# Voltage_Sense_Board.net
KiCad netlist of a schematic drawn in Altium Designer
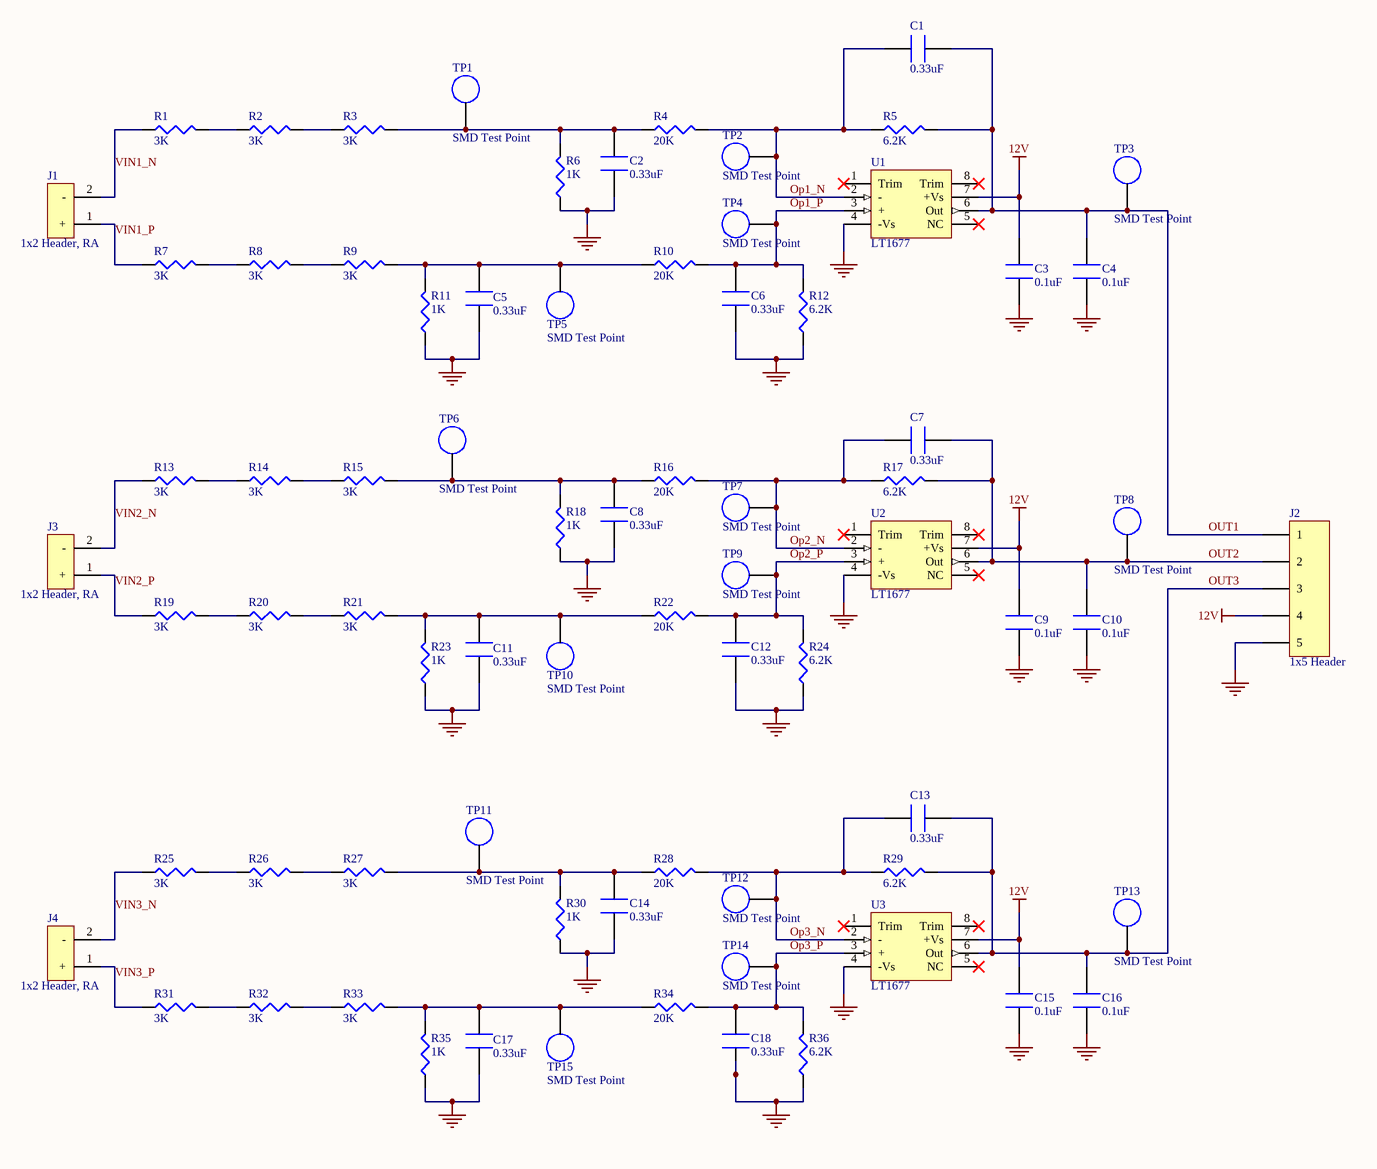
[diagram p0: Voltage Sense Board.SchDoc]

(export (version "E")
  (design (tool "Eeschema 10.0.6"))
  (components
    (comp (ref "C1")
      (value "0.33uF")
      (description "CAP CER 0.33UF 50V X7R 0805")
      (fields
        (field (name "MANUFACTURER") "Samsung")
        (field (name "MANUFACTURER PART NUMBER") "CL21B334KBFVPNE")
      )
      (libsource (lib "V_Sense_Schlib") (part "CL21B334KBFVPNE"))
    )
    (comp (ref "C2")
      (value "0.33uF")
      (description "CAP CER 0.33UF 50V X7R 0805")
      (fields
        (field (name "MANUFACTURER") "Samsung")
        (field (name "MANUFACTURER PART NUMBER") "CL21B334KBFVPNE")
      )
      (libsource (lib "V_Sense_Schlib") (part "CL21B334KBFVPNE"))
    )
    (comp (ref "C3")
      (value "0.1uF")
      (description "CAP CER 0.1UF 50V X7R 0805")
      (fields
        (field (name "MANUFACTURER") "Samsung")
        (field (name "MANUFACTURER PART NUMBER") "CL21B104KBCWPNC")
      )
      (libsource (lib "V_Sense_Schlib") (part "CL21B104KBCWPNC"))
    )
    (comp (ref "C4")
      (value "0.1uF")
      (description "CAP CER 0.1UF 50V X7R 0805")
      (fields
        (field (name "MANUFACTURER") "Samsung")
        (field (name "MANUFACTURER PART NUMBER") "CL21B104KBCWPNC")
      )
      (libsource (lib "V_Sense_Schlib") (part "CL21B104KBCWPNC"))
    )
    (comp (ref "C5")
      (value "0.33uF")
      (description "CAP CER 0.33UF 50V X7R 0805")
      (fields
        (field (name "MANUFACTURER") "Samsung")
        (field (name "MANUFACTURER PART NUMBER") "CL21B334KBFVPNE")
      )
      (libsource (lib "V_Sense_Schlib") (part "CL21B334KBFVPNE"))
    )
    (comp (ref "C6")
      (value "0.33uF")
      (description "CAP CER 0.33UF 50V X7R 0805")
      (fields
        (field (name "MANUFACTURER") "Samsung")
        (field (name "MANUFACTURER PART NUMBER") "CL21B334KBFVPNE")
      )
      (libsource (lib "V_Sense_Schlib") (part "CL21B334KBFVPNE"))
    )
    (comp (ref "C7")
      (value "0.33uF")
      (description "CAP CER 0.33UF 50V X7R 0805")
      (fields
        (field (name "MANUFACTURER") "Samsung")
        (field (name "MANUFACTURER PART NUMBER") "CL21B334KBFVPNE")
      )
      (libsource (lib "V_Sense_Schlib") (part "CL21B334KBFVPNE"))
    )
    (comp (ref "C8")
      (value "0.33uF")
      (description "CAP CER 0.33UF 50V X7R 0805")
      (fields
        (field (name "MANUFACTURER") "Samsung")
        (field (name "MANUFACTURER PART NUMBER") "CL21B334KBFVPNE")
      )
      (libsource (lib "V_Sense_Schlib") (part "CL21B334KBFVPNE"))
    )
    (comp (ref "C9")
      (value "0.1uF")
      (description "CAP CER 0.1UF 50V X7R 0805")
      (fields
        (field (name "MANUFACTURER") "Samsung")
        (field (name "MANUFACTURER PART NUMBER") "CL21B104KBCWPNC")
      )
      (libsource (lib "V_Sense_Schlib") (part "CL21B104KBCWPNC"))
    )
    (comp (ref "C10")
      (value "0.1uF")
      (description "CAP CER 0.1UF 50V X7R 0805")
      (fields
        (field (name "MANUFACTURER") "Samsung")
        (field (name "MANUFACTURER PART NUMBER") "CL21B104KBCWPNC")
      )
      (libsource (lib "V_Sense_Schlib") (part "CL21B104KBCWPNC"))
    )
    (comp (ref "C11")
      (value "0.33uF")
      (description "CAP CER 0.33UF 50V X7R 0805")
      (fields
        (field (name "MANUFACTURER") "Samsung")
        (field (name "MANUFACTURER PART NUMBER") "CL21B334KBFVPNE")
      )
      (libsource (lib "V_Sense_Schlib") (part "CL21B334KBFVPNE"))
    )
    (comp (ref "C12")
      (value "0.33uF")
      (description "CAP CER 0.33UF 50V X7R 0805")
      (fields
        (field (name "MANUFACTURER") "Samsung")
        (field (name "MANUFACTURER PART NUMBER") "CL21B334KBFVPNE")
      )
      (libsource (lib "V_Sense_Schlib") (part "CL21B334KBFVPNE"))
    )
    (comp (ref "C13")
      (value "0.33uF")
      (description "CAP CER 0.33UF 50V X7R 0805")
      (fields
        (field (name "MANUFACTURER") "Samsung")
        (field (name "MANUFACTURER PART NUMBER") "CL21B334KBFVPNE")
      )
      (libsource (lib "V_Sense_Schlib") (part "CL21B334KBFVPNE"))
    )
    (comp (ref "C14")
      (value "0.33uF")
      (description "CAP CER 0.33UF 50V X7R 0805")
      (fields
        (field (name "MANUFACTURER") "Samsung")
        (field (name "MANUFACTURER PART NUMBER") "CL21B334KBFVPNE")
      )
      (libsource (lib "V_Sense_Schlib") (part "CL21B334KBFVPNE"))
    )
    (comp (ref "C15")
      (value "0.1uF")
      (description "CAP CER 0.1UF 50V X7R 0805")
      (fields
        (field (name "MANUFACTURER") "Samsung")
        (field (name "MANUFACTURER PART NUMBER") "CL21B104KBCWPNC")
      )
      (libsource (lib "V_Sense_Schlib") (part "CL21B104KBCWPNC"))
    )
    (comp (ref "C16")
      (value "0.1uF")
      (description "CAP CER 0.1UF 50V X7R 0805")
      (fields
        (field (name "MANUFACTURER") "Samsung")
        (field (name "MANUFACTURER PART NUMBER") "CL21B104KBCWPNC")
      )
      (libsource (lib "V_Sense_Schlib") (part "CL21B104KBCWPNC"))
    )
    (comp (ref "C17")
      (value "0.33uF")
      (description "CAP CER 0.33UF 50V X7R 0805")
      (fields
        (field (name "MANUFACTURER") "Samsung")
        (field (name "MANUFACTURER PART NUMBER") "CL21B334KBFVPNE")
      )
      (libsource (lib "V_Sense_Schlib") (part "CL21B334KBFVPNE"))
    )
    (comp (ref "C18")
      (value "0.33uF")
      (description "CAP CER 0.33UF 50V X7R 0805")
      (fields
        (field (name "MANUFACTURER") "Samsung")
        (field (name "MANUFACTURER PART NUMBER") "CL21B334KBFVPNE")
      )
      (libsource (lib "V_Sense_Schlib") (part "CL21B334KBFVPNE"))
    )
    (comp (ref "J1")
      (value "1x2 Header, RA")
      (description "HEADER, RIGHT ANGLE, 2WAY")
      (fields (field (name "MANUFACTURER") "Molex") (field (name "MANUFACTURER PART NUMBER") "43650-0205"))
      (libsource (lib "V_Sense_Schlib") (part "43650-0205"))
    )
    (comp (ref "J2")
      (value "1x5 Header")
      (description "CONN HEADER VERT SGL 5POS GOLD")
      (fields (field (name "MANUFACTURER") "3M") (field (name "MANUFACTURER PART NUMBER") "961105-6404-AR"))
      (libsource (lib "V_Sense_Schlib") (part "961105-6404-AR"))
    )
    (comp (ref "J3")
      (value "1x2 Header, RA")
      (description "HEADER, RIGHT ANGLE, 2WAY")
      (fields (field (name "MANUFACTURER") "Molex") (field (name "MANUFACTURER PART NUMBER") "43650-0205"))
      (libsource (lib "V_Sense_Schlib") (part "43650-0205"))
    )
    (comp (ref "J4")
      (value "1x2 Header, RA")
      (description "HEADER, RIGHT ANGLE, 2WAY")
      (fields (field (name "MANUFACTURER") "Molex") (field (name "MANUFACTURER PART NUMBER") "43650-0205"))
      (libsource (lib "V_Sense_Schlib") (part "43650-0205"))
    )
    (comp (ref "R1")
      (value "3K")
      (description "RES SMD 3K OHM 1% 0.4W 0805")
      (fields (field (name "MANUFACTURER") "Rohm") (field (name "MANUFACTURER PART NUMBER") "ESR10EZPF3001"))
      (libsource (lib "V_Sense_Schlib") (part "ESR10EZPF3001"))
    )
    (comp (ref "R2")
      (value "3K")
      (description "RES SMD 3K OHM 1% 0.4W 0805")
      (fields (field (name "MANUFACTURER") "Rohm") (field (name "MANUFACTURER PART NUMBER") "ESR10EZPF3001"))
      (libsource (lib "V_Sense_Schlib") (part "ESR10EZPF3001"))
    )
    (comp (ref "R3")
      (value "3K")
      (description "RES SMD 3K OHM 1% 0.4W 0805")
      (fields (field (name "MANUFACTURER") "Rohm") (field (name "MANUFACTURER PART NUMBER") "ESR10EZPF3001"))
      (libsource (lib "V_Sense_Schlib") (part "ESR10EZPF3001"))
    )
    (comp (ref "R4")
      (value "20K")
      (description "RES 20K OHM 0.1% 1/5W 0805")
      (fields
        (field (name "MANUFACTURER") "Vishay Dale")
        (field (name "MANUFACTURER PART NUMBER") "TNPW080520K0BEEA")
      )
      (libsource (lib "V_Sense_Schlib") (part "TNPW080520K0BEEA"))
    )
    (comp (ref "R5")
      (value "6.2K")
      (description "RES SMD 6.2K OHM 0.1% 1/8W 0805")
      (fields
        (field (name "MANUFACTURER") "Panasonic")
        (field (name "MANUFACTURER PART NUMBER") "ERA6AEB622V")
      )
      (libsource (lib "V_Sense_Schlib") (part "ERA6AEB622V"))
    )
    (comp (ref "R6")
      (value "1K")
      (description "RES SMD 1K OHM 0.1% 1/4W 0805")
      (fields
        (field (name "MANUFACTURER") "TE Connectivity")
        (field (name "MANUFACTURER PART NUMBER") "1-2176092-8")
      )
      (libsource (lib "V_Sense_Schlib") (part "1-2176092-8"))
    )
    (comp (ref "R7")
      (value "3K")
      (description "RES SMD 3K OHM 1% 0.4W 0805")
      (fields (field (name "MANUFACTURER") "Rohm") (field (name "MANUFACTURER PART NUMBER") "ESR10EZPF3001"))
      (libsource (lib "V_Sense_Schlib") (part "ESR10EZPF3001"))
    )
    (comp (ref "R8")
      (value "3K")
      (description "RES SMD 3K OHM 1% 0.4W 0805")
      (fields (field (name "MANUFACTURER") "Rohm") (field (name "MANUFACTURER PART NUMBER") "ESR10EZPF3001"))
      (libsource (lib "V_Sense_Schlib") (part "ESR10EZPF3001"))
    )
    (comp (ref "R9")
      (value "3K")
      (description "RES SMD 3K OHM 1% 0.4W 0805")
      (fields (field (name "MANUFACTURER") "Rohm") (field (name "MANUFACTURER PART NUMBER") "ESR10EZPF3001"))
      (libsource (lib "V_Sense_Schlib") (part "ESR10EZPF3001"))
    )
    (comp (ref "R10")
      (value "20K")
      (description "RES 20K OHM 0.1% 1/5W 0805")
      (fields
        (field (name "MANUFACTURER") "Vishay Dale")
        (field (name "MANUFACTURER PART NUMBER") "TNPW080520K0BEEA")
      )
      (libsource (lib "V_Sense_Schlib") (part "TNPW080520K0BEEA"))
    )
    (comp (ref "R11")
      (value "1K")
      (description "RES SMD 1K OHM 0.1% 1/4W 0805")
      (fields
        (field (name "MANUFACTURER") "TE Connectivity")
        (field (name "MANUFACTURER PART NUMBER") "1-2176092-8")
      )
      (libsource (lib "V_Sense_Schlib") (part "1-2176092-8"))
    )
    (comp (ref "R12")
      (value "6.2K")
      (description "RES SMD 6.2K OHM 0.1% 1/8W 0805")
      (fields
        (field (name "MANUFACTURER") "Panasonic")
        (field (name "MANUFACTURER PART NUMBER") "ERA6AEB622V")
      )
      (libsource (lib "V_Sense_Schlib") (part "ERA6AEB622V"))
    )
    (comp (ref "R13")
      (value "3K")
      (description "RES SMD 3K OHM 1% 0.4W 0805")
      (fields (field (name "MANUFACTURER") "Rohm") (field (name "MANUFACTURER PART NUMBER") "ESR10EZPF3001"))
      (libsource (lib "V_Sense_Schlib") (part "ESR10EZPF3001"))
    )
    (comp (ref "R14")
      (value "3K")
      (description "RES SMD 3K OHM 1% 0.4W 0805")
      (fields (field (name "MANUFACTURER") "Rohm") (field (name "MANUFACTURER PART NUMBER") "ESR10EZPF3001"))
      (libsource (lib "V_Sense_Schlib") (part "ESR10EZPF3001"))
    )
    (comp (ref "R15")
      (value "3K")
      (description "RES SMD 3K OHM 1% 0.4W 0805")
      (fields (field (name "MANUFACTURER") "Rohm") (field (name "MANUFACTURER PART NUMBER") "ESR10EZPF3001"))
      (libsource (lib "V_Sense_Schlib") (part "ESR10EZPF3001"))
    )
    (comp (ref "R16")
      (value "20K")
      (description "RES 20K OHM 0.1% 1/5W 0805")
      (fields
        (field (name "MANUFACTURER") "Vishay Dale")
        (field (name "MANUFACTURER PART NUMBER") "TNPW080520K0BEEA")
      )
      (libsource (lib "V_Sense_Schlib") (part "TNPW080520K0BEEA"))
    )
    (comp (ref "R17")
      (value "6.2K")
      (description "RES SMD 6.2K OHM 0.1% 1/8W 0805")
      (fields
        (field (name "MANUFACTURER") "Panasonic")
        (field (name "MANUFACTURER PART NUMBER") "ERA6AEB622V")
      )
      (libsource (lib "V_Sense_Schlib") (part "ERA6AEB622V"))
    )
    (comp (ref "R18")
      (value "1K")
      (description "RES SMD 1K OHM 0.1% 1/4W 0805")
      (fields
        (field (name "MANUFACTURER") "TE Connectivity")
        (field (name "MANUFACTURER PART NUMBER") "1-2176092-8")
      )
      (libsource (lib "V_Sense_Schlib") (part "1-2176092-8"))
    )
    (comp (ref "R19")
      (value "3K")
      (description "RES SMD 3K OHM 1% 0.4W 0805")
      (fields (field (name "MANUFACTURER") "Rohm") (field (name "MANUFACTURER PART NUMBER") "ESR10EZPF3001"))
      (libsource (lib "V_Sense_Schlib") (part "ESR10EZPF3001"))
    )
    (comp (ref "R20")
      (value "3K")
      (description "RES SMD 3K OHM 1% 0.4W 0805")
      (fields (field (name "MANUFACTURER") "Rohm") (field (name "MANUFACTURER PART NUMBER") "ESR10EZPF3001"))
      (libsource (lib "V_Sense_Schlib") (part "ESR10EZPF3001"))
    )
    (comp (ref "R21")
      (value "3K")
      (description "RES SMD 3K OHM 1% 0.4W 0805")
      (fields (field (name "MANUFACTURER") "Rohm") (field (name "MANUFACTURER PART NUMBER") "ESR10EZPF3001"))
      (libsource (lib "V_Sense_Schlib") (part "ESR10EZPF3001"))
    )
    (comp (ref "R22")
      (value "20K")
      (description "RES 20K OHM 0.1% 1/5W 0805")
      (fields
        (field (name "MANUFACTURER") "Vishay Dale")
        (field (name "MANUFACTURER PART NUMBER") "TNPW080520K0BEEA")
      )
      (libsource (lib "V_Sense_Schlib") (part "TNPW080520K0BEEA"))
    )
    (comp (ref "R23")
      (value "1K")
      (description "RES SMD 1K OHM 0.1% 1/4W 0805")
      (fields
        (field (name "MANUFACTURER") "TE Connectivity")
        (field (name "MANUFACTURER PART NUMBER") "1-2176092-8")
      )
      (libsource (lib "V_Sense_Schlib") (part "1-2176092-8"))
    )
    (comp (ref "R24")
      (value "6.2K")
      (description "RES SMD 6.2K OHM 0.1% 1/8W 0805")
      (fields
        (field (name "MANUFACTURER") "Panasonic")
        (field (name "MANUFACTURER PART NUMBER") "ERA6AEB622V")
      )
      (libsource (lib "V_Sense_Schlib") (part "ERA6AEB622V"))
    )
    (comp (ref "R25")
      (value "3K")
      (description "RES SMD 3K OHM 1% 0.4W 0805")
      (fields (field (name "MANUFACTURER") "Rohm") (field (name "MANUFACTURER PART NUMBER") "ESR10EZPF3001"))
      (libsource (lib "V_Sense_Schlib") (part "ESR10EZPF3001"))
    )
    (comp (ref "R26")
      (value "3K")
      (description "RES SMD 3K OHM 1% 0.4W 0805")
      (fields (field (name "MANUFACTURER") "Rohm") (field (name "MANUFACTURER PART NUMBER") "ESR10EZPF3001"))
      (libsource (lib "V_Sense_Schlib") (part "ESR10EZPF3001"))
    )
    (comp (ref "R27")
      (value "3K")
      (description "RES SMD 3K OHM 1% 0.4W 0805")
      (fields (field (name "MANUFACTURER") "Rohm") (field (name "MANUFACTURER PART NUMBER") "ESR10EZPF3001"))
      (libsource (lib "V_Sense_Schlib") (part "ESR10EZPF3001"))
    )
    (comp (ref "R28")
      (value "20K")
      (description "RES 20K OHM 0.1% 1/5W 0805")
      (fields
        (field (name "MANUFACTURER") "Vishay Dale")
        (field (name "MANUFACTURER PART NUMBER") "TNPW080520K0BEEA")
      )
      (libsource (lib "V_Sense_Schlib") (part "TNPW080520K0BEEA"))
    )
    (comp (ref "R29")
      (value "6.2K")
      (description "RES SMD 6.2K OHM 0.1% 1/8W 0805")
      (fields
        (field (name "MANUFACTURER") "Panasonic")
        (field (name "MANUFACTURER PART NUMBER") "ERA6AEB622V")
      )
      (libsource (lib "V_Sense_Schlib") (part "ERA6AEB622V"))
    )
    (comp (ref "R30")
      (value "1K")
      (description "RES SMD 1K OHM 0.1% 1/4W 0805")
      (fields
        (field (name "MANUFACTURER") "TE Connectivity")
        (field (name "MANUFACTURER PART NUMBER") "1-2176092-8")
      )
      (libsource (lib "V_Sense_Schlib") (part "1-2176092-8"))
    )
    (comp (ref "R31")
      (value "3K")
      (description "RES SMD 3K OHM 1% 0.4W 0805")
      (fields (field (name "MANUFACTURER") "Rohm") (field (name "MANUFACTURER PART NUMBER") "ESR10EZPF3001"))
      (libsource (lib "V_Sense_Schlib") (part "ESR10EZPF3001"))
    )
    (comp (ref "R32")
      (value "3K")
      (description "RES SMD 3K OHM 1% 0.4W 0805")
      (fields (field (name "MANUFACTURER") "Rohm") (field (name "MANUFACTURER PART NUMBER") "ESR10EZPF3001"))
      (libsource (lib "V_Sense_Schlib") (part "ESR10EZPF3001"))
    )
    (comp (ref "R33")
      (value "3K")
      (description "RES SMD 3K OHM 1% 0.4W 0805")
      (fields (field (name "MANUFACTURER") "Rohm") (field (name "MANUFACTURER PART NUMBER") "ESR10EZPF3001"))
      (libsource (lib "V_Sense_Schlib") (part "ESR10EZPF3001"))
    )
    (comp (ref "R34")
      (value "20K")
      (description "RES 20K OHM 0.1% 1/5W 0805")
      (fields
        (field (name "MANUFACTURER") "Vishay Dale")
        (field (name "MANUFACTURER PART NUMBER") "TNPW080520K0BEEA")
      )
      (libsource (lib "V_Sense_Schlib") (part "TNPW080520K0BEEA"))
    )
    (comp (ref "R35")
      (value "1K")
      (description "RES SMD 1K OHM 0.1% 1/4W 0805")
      (fields
        (field (name "MANUFACTURER") "TE Connectivity")
        (field (name "MANUFACTURER PART NUMBER") "1-2176092-8")
      )
      (libsource (lib "V_Sense_Schlib") (part "1-2176092-8"))
    )
    (comp (ref "R36")
      (value "6.2K")
      (description "RES SMD 6.2K OHM 0.1% 1/8W 0805")
      (fields
        (field (name "MANUFACTURER") "Panasonic")
        (field (name "MANUFACTURER PART NUMBER") "ERA6AEB622V")
      )
      (libsource (lib "V_Sense_Schlib") (part "ERA6AEB622V"))
    )
    (comp (ref "TP1")
      (value "SMD Test Point")
      (description "Phosphor Bronze Contact Miniature Silver Plated Surface Mount Test Points")
      (fields
        (field (name "MANUFACTURER") "Keystone Electronics")
        (field (name "MANUFACTURER PART NUMBER") "5019")
      )
      (libsource (lib "V_Sense_Schlib") (part "5019"))
    )
    (comp (ref "TP2")
      (value "SMD Test Point")
      (description "Phosphor Bronze Contact Miniature Silver Plated Surface Mount Test Points")
      (fields
        (field (name "MANUFACTURER") "Keystone Electronics")
        (field (name "MANUFACTURER PART NUMBER") "5019")
      )
      (libsource (lib "V_Sense_Schlib") (part "5019"))
    )
    (comp (ref "TP3")
      (value "SMD Test Point")
      (description "Phosphor Bronze Contact Miniature Silver Plated Surface Mount Test Points")
      (fields
        (field (name "MANUFACTURER") "Keystone Electronics")
        (field (name "MANUFACTURER PART NUMBER") "5019")
      )
      (libsource (lib "V_Sense_Schlib") (part "5019"))
    )
    (comp (ref "TP4")
      (value "SMD Test Point")
      (description "Phosphor Bronze Contact Miniature Silver Plated Surface Mount Test Points")
      (fields
        (field (name "MANUFACTURER") "Keystone Electronics")
        (field (name "MANUFACTURER PART NUMBER") "5019")
      )
      (libsource (lib "V_Sense_Schlib") (part "5019"))
    )
    (comp (ref "TP5")
      (value "SMD Test Point")
      (description "Phosphor Bronze Contact Miniature Silver Plated Surface Mount Test Points")
      (fields
        (field (name "MANUFACTURER") "Keystone Electronics")
        (field (name "MANUFACTURER PART NUMBER") "5019")
      )
      (libsource (lib "V_Sense_Schlib") (part "5019"))
    )
    (comp (ref "TP6")
      (value "SMD Test Point")
      (description "Phosphor Bronze Contact Miniature Silver Plated Surface Mount Test Points")
      (fields
        (field (name "MANUFACTURER") "Keystone Electronics")
        (field (name "MANUFACTURER PART NUMBER") "5019")
      )
      (libsource (lib "V_Sense_Schlib") (part "5019"))
    )
    (comp (ref "TP7")
      (value "SMD Test Point")
      (description "Phosphor Bronze Contact Miniature Silver Plated Surface Mount Test Points")
      (fields
        (field (name "MANUFACTURER") "Keystone Electronics")
        (field (name "MANUFACTURER PART NUMBER") "5019")
      )
      (libsource (lib "V_Sense_Schlib") (part "5019"))
    )
    (comp (ref "TP8")
      (value "SMD Test Point")
      (description "Phosphor Bronze Contact Miniature Silver Plated Surface Mount Test Points")
      (fields
        (field (name "MANUFACTURER") "Keystone Electronics")
        (field (name "MANUFACTURER PART NUMBER") "5019")
      )
      (libsource (lib "V_Sense_Schlib") (part "5019"))
    )
    (comp (ref "TP9")
      (value "SMD Test Point")
      (description "Phosphor Bronze Contact Miniature Silver Plated Surface Mount Test Points")
      (fields
        (field (name "MANUFACTURER") "Keystone Electronics")
        (field (name "MANUFACTURER PART NUMBER") "5019")
      )
      (libsource (lib "V_Sense_Schlib") (part "5019"))
    )
    (comp (ref "TP10")
      (value "SMD Test Point")
      (description "Phosphor Bronze Contact Miniature Silver Plated Surface Mount Test Points")
      (fields
        (field (name "MANUFACTURER") "Keystone Electronics")
        (field (name "MANUFACTURER PART NUMBER") "5019")
      )
      (libsource (lib "V_Sense_Schlib") (part "5019"))
    )
    (comp (ref "TP11")
      (value "SMD Test Point")
      (description "Phosphor Bronze Contact Miniature Silver Plated Surface Mount Test Points")
      (fields
        (field (name "MANUFACTURER") "Keystone Electronics")
        (field (name "MANUFACTURER PART NUMBER") "5019")
      )
      (libsource (lib "V_Sense_Schlib") (part "5019"))
    )
    (comp (ref "TP12")
      (value "SMD Test Point")
      (description "Phosphor Bronze Contact Miniature Silver Plated Surface Mount Test Points")
      (fields
        (field (name "MANUFACTURER") "Keystone Electronics")
        (field (name "MANUFACTURER PART NUMBER") "5019")
      )
      (libsource (lib "V_Sense_Schlib") (part "5019"))
    )
    (comp (ref "TP13")
      (value "SMD Test Point")
      (description "Phosphor Bronze Contact Miniature Silver Plated Surface Mount Test Points")
      (fields
        (field (name "MANUFACTURER") "Keystone Electronics")
        (field (name "MANUFACTURER PART NUMBER") "5019")
      )
      (libsource (lib "V_Sense_Schlib") (part "5019"))
    )
    (comp (ref "TP14")
      (value "SMD Test Point")
      (description "Phosphor Bronze Contact Miniature Silver Plated Surface Mount Test Points")
      (fields
        (field (name "MANUFACTURER") "Keystone Electronics")
        (field (name "MANUFACTURER PART NUMBER") "5019")
      )
      (libsource (lib "V_Sense_Schlib") (part "5019"))
    )
    (comp (ref "TP15")
      (value "SMD Test Point")
      (description "Phosphor Bronze Contact Miniature Silver Plated Surface Mount Test Points")
      (fields
        (field (name "MANUFACTURER") "Keystone Electronics")
        (field (name "MANUFACTURER PART NUMBER") "5019")
      )
      (libsource (lib "V_Sense_Schlib") (part "5019"))
    )
    (comp (ref "U1")
      (value "LT1677")
      (description "IC OPAMP GP 7.2MHZ RRO 8SO")
      (fields
        (field (name "MANUFACTURER") "Analog Devices / Linear Technology")
        (field (name "MANUFACTURER PART NUMBER") "LT1677IS8#TRPBF")
      )
      (libsource (lib "V_Sense_Schlib") (part "LT1677IS8#TRPBF"))
    )
    (comp (ref "U2")
      (value "LT1677")
      (description "IC OPAMP GP 7.2MHZ RRO 8SO")
      (fields
        (field (name "MANUFACTURER") "Analog Devices / Linear Technology")
        (field (name "MANUFACTURER PART NUMBER") "LT1677IS8#TRPBF")
      )
      (libsource (lib "V_Sense_Schlib") (part "LT1677IS8#TRPBF"))
    )
    (comp (ref "U3")
      (value "LT1677")
      (description "IC OPAMP GP 7.2MHZ RRO 8SO")
      (fields
        (field (name "MANUFACTURER") "Analog Devices / Linear Technology")
        (field (name "MANUFACTURER PART NUMBER") "LT1677IS8#TRPBF")
      )
      (libsource (lib "V_Sense_Schlib") (part "LT1677IS8#TRPBF"))
    )
  )
  (nets
    (net (code "1") (name "/OUT1") (class "Default")
      (node (ref "C1") (pin "2") (pinfunction "2_2") (pintype "passive"))
      (node (ref "C4") (pin "2") (pinfunction "2_2") (pintype "passive"))
      (node (ref "J2") (pin "1") (pinfunction "1_1") (pintype "passive"))
      (node (ref "R5") (pin "2") (pinfunction "2_2") (pintype "passive"))
      (node (ref "TP3") (pin "1") (pinfunction "1_1") (pintype "passive"))
      (node (ref "U1") (pin "6") (pinfunction "Out_6") (pintype "output"))
    )
    (net (code "2") (name "/OUT2") (class "Default")
      (node (ref "C10") (pin "2") (pinfunction "2_2") (pintype "passive"))
      (node (ref "C7") (pin "2") (pinfunction "2_2") (pintype "passive"))
      (node (ref "J2") (pin "2") (pinfunction "2_2") (pintype "passive"))
      (node (ref "R17") (pin "2") (pinfunction "2_2") (pintype "passive"))
      (node (ref "TP8") (pin "1") (pinfunction "1_1") (pintype "passive"))
      (node (ref "U2") (pin "6") (pinfunction "Out_6") (pintype "output"))
    )
    (net (code "3") (name "/OUT3") (class "Default")
      (node (ref "C13") (pin "2") (pinfunction "2_2") (pintype "passive"))
      (node (ref "C16") (pin "2") (pinfunction "2_2") (pintype "passive"))
      (node (ref "J2") (pin "3") (pinfunction "3_3") (pintype "passive"))
      (node (ref "R29") (pin "2") (pinfunction "2_2") (pintype "passive"))
      (node (ref "TP13") (pin "1") (pinfunction "1_1") (pintype "passive"))
      (node (ref "U3") (pin "6") (pinfunction "Out_6") (pintype "output"))
    )
    (net (code "4") (name "/Op1_N") (class "Default")
      (node (ref "C1") (pin "1") (pinfunction "1_1") (pintype "passive"))
      (node (ref "R4") (pin "2") (pinfunction "2_2") (pintype "passive"))
      (node (ref "R5") (pin "1") (pinfunction "1_1") (pintype "passive"))
      (node (ref "TP2") (pin "1") (pinfunction "1_1") (pintype "passive"))
      (node (ref "U1") (pin "2") (pinfunction "-_2") (pintype "input"))
    )
    (net (code "5") (name "/Op1_P") (class "Default")
      (node (ref "C6") (pin "2") (pinfunction "2_2") (pintype "passive"))
      (node (ref "R10") (pin "2") (pinfunction "2_2") (pintype "passive"))
      (node (ref "R12") (pin "2") (pinfunction "2_2") (pintype "passive"))
      (node (ref "TP4") (pin "1") (pinfunction "1_1") (pintype "passive"))
      (node (ref "U1") (pin "3") (pinfunction "+_3") (pintype "input"))
    )
    (net (code "6") (name "/Op2_N") (class "Default")
      (node (ref "C7") (pin "1") (pinfunction "1_1") (pintype "passive"))
      (node (ref "R16") (pin "2") (pinfunction "2_2") (pintype "passive"))
      (node (ref "R17") (pin "1") (pinfunction "1_1") (pintype "passive"))
      (node (ref "TP7") (pin "1") (pinfunction "1_1") (pintype "passive"))
      (node (ref "U2") (pin "2") (pinfunction "-_2") (pintype "input"))
    )
    (net (code "7") (name "/Op2_P") (class "Default")
      (node (ref "C12") (pin "2") (pinfunction "2_2") (pintype "passive"))
      (node (ref "R22") (pin "2") (pinfunction "2_2") (pintype "passive"))
      (node (ref "R24") (pin "2") (pinfunction "2_2") (pintype "passive"))
      (node (ref "TP9") (pin "1") (pinfunction "1_1") (pintype "passive"))
      (node (ref "U2") (pin "3") (pinfunction "+_3") (pintype "input"))
    )
    (net (code "8") (name "/Op3_N") (class "Default")
      (node (ref "C13") (pin "1") (pinfunction "1_1") (pintype "passive"))
      (node (ref "R28") (pin "2") (pinfunction "2_2") (pintype "passive"))
      (node (ref "R29") (pin "1") (pinfunction "1_1") (pintype "passive"))
      (node (ref "TP12") (pin "1") (pinfunction "1_1") (pintype "passive"))
      (node (ref "U3") (pin "2") (pinfunction "-_2") (pintype "input"))
    )
    (net (code "9") (name "/Op3_P") (class "Default")
      (node (ref "C18") (pin "2") (pinfunction "2_2") (pintype "passive"))
      (node (ref "R34") (pin "2") (pinfunction "2_2") (pintype "passive"))
      (node (ref "R36") (pin "2") (pinfunction "2_2") (pintype "passive"))
      (node (ref "TP14") (pin "1") (pinfunction "1_1") (pintype "passive"))
      (node (ref "U3") (pin "3") (pinfunction "+_3") (pintype "input"))
    )
    (net (code "10") (name "/VIN1_N") (class "Default")
      (node (ref "J1") (pin "2") (pinfunction "-_2") (pintype "passive"))
      (node (ref "R1") (pin "1") (pinfunction "1_1") (pintype "passive"))
    )
    (net (code "11") (name "/VIN1_P") (class "Default")
      (node (ref "J1") (pin "1") (pinfunction "+_1") (pintype "passive"))
      (node (ref "R7") (pin "1") (pinfunction "1_1") (pintype "passive"))
    )
    (net (code "12") (name "/VIN2_N") (class "Default")
      (node (ref "J3") (pin "2") (pinfunction "-_2") (pintype "passive"))
      (node (ref "R13") (pin "1") (pinfunction "1_1") (pintype "passive"))
    )
    (net (code "13") (name "/VIN2_P") (class "Default")
      (node (ref "J3") (pin "1") (pinfunction "+_1") (pintype "passive"))
      (node (ref "R19") (pin "1") (pinfunction "1_1") (pintype "passive"))
    )
    (net (code "14") (name "/VIN3_N") (class "Default")
      (node (ref "J4") (pin "2") (pinfunction "-_2") (pintype "passive"))
      (node (ref "R25") (pin "1") (pinfunction "1_1") (pintype "passive"))
    )
    (net (code "15") (name "/VIN3_P") (class "Default")
      (node (ref "J4") (pin "1") (pinfunction "+_1") (pintype "passive"))
      (node (ref "R31") (pin "1") (pinfunction "1_1") (pintype "passive"))
    )
    (net (code "16") (name "12V") (class "Default")
      (node (ref "C15") (pin "2") (pinfunction "2_2") (pintype "passive"))
      (node (ref "C3") (pin "2") (pinfunction "2_2") (pintype "passive"))
      (node (ref "C9") (pin "2") (pinfunction "2_2") (pintype "passive"))
      (node (ref "J2") (pin "4") (pinfunction "4_4") (pintype "passive"))
      (node (ref "U1") (pin "7") (pinfunction "+Vs_7") (pintype "power_in"))
      (node (ref "U2") (pin "7") (pinfunction "+Vs_7") (pintype "power_in"))
      (node (ref "U3") (pin "7") (pinfunction "+Vs_7") (pintype "power_in"))
    )
    (net (code "17") (name "GND") (class "Default")
      (node (ref "C10") (pin "1") (pinfunction "1_1") (pintype "passive"))
      (node (ref "C11") (pin "1") (pinfunction "1_1") (pintype "passive"))
      (node (ref "C12") (pin "1") (pinfunction "1_1") (pintype "passive"))
      (node (ref "C14") (pin "1") (pinfunction "1_1") (pintype "passive"))
      (node (ref "C15") (pin "1") (pinfunction "1_1") (pintype "passive"))
      (node (ref "C16") (pin "1") (pinfunction "1_1") (pintype "passive"))
      (node (ref "C17") (pin "1") (pinfunction "1_1") (pintype "passive"))
      (node (ref "C18") (pin "1") (pinfunction "1_1") (pintype "passive"))
      (node (ref "C2") (pin "1") (pinfunction "1_1") (pintype "passive"))
      (node (ref "C3") (pin "1") (pinfunction "1_1") (pintype "passive"))
      (node (ref "C4") (pin "1") (pinfunction "1_1") (pintype "passive"))
      (node (ref "C5") (pin "1") (pinfunction "1_1") (pintype "passive"))
      (node (ref "C6") (pin "1") (pinfunction "1_1") (pintype "passive"))
      (node (ref "C8") (pin "1") (pinfunction "1_1") (pintype "passive"))
      (node (ref "C9") (pin "1") (pinfunction "1_1") (pintype "passive"))
      (node (ref "J2") (pin "5") (pinfunction "5_5") (pintype "passive"))
      (node (ref "R11") (pin "1") (pinfunction "1_1") (pintype "passive"))
      (node (ref "R12") (pin "1") (pinfunction "1_1") (pintype "passive"))
      (node (ref "R18") (pin "1") (pinfunction "1_1") (pintype "passive"))
      (node (ref "R23") (pin "1") (pinfunction "1_1") (pintype "passive"))
      (node (ref "R24") (pin "1") (pinfunction "1_1") (pintype "passive"))
      (node (ref "R30") (pin "1") (pinfunction "1_1") (pintype "passive"))
      (node (ref "R35") (pin "1") (pinfunction "1_1") (pintype "passive"))
      (node (ref "R36") (pin "1") (pinfunction "1_1") (pintype "passive"))
      (node (ref "R6") (pin "1") (pinfunction "1_1") (pintype "passive"))
      (node (ref "U1") (pin "4") (pinfunction "-Vs_4") (pintype "power_in"))
      (node (ref "U2") (pin "4") (pinfunction "-Vs_4") (pintype "power_in"))
      (node (ref "U3") (pin "4") (pinfunction "-Vs_4") (pintype "power_in"))
    )
    (net (code "18") (name "Net-(C2-Pad2)") (class "Default")
      (node (ref "C2") (pin "2") (pinfunction "2_2") (pintype "passive"))
      (node (ref "R3") (pin "2") (pinfunction "2_2") (pintype "passive"))
      (node (ref "R4") (pin "1") (pinfunction "1_1") (pintype "passive"))
      (node (ref "R6") (pin "2") (pinfunction "2_2") (pintype "passive"))
      (node (ref "TP1") (pin "1") (pinfunction "1_1") (pintype "passive"))
    )
    (net (code "19") (name "Net-(C5-Pad2)") (class "Default")
      (node (ref "C5") (pin "2") (pinfunction "2_2") (pintype "passive"))
      (node (ref "R10") (pin "1") (pinfunction "1_1") (pintype "passive"))
      (node (ref "R11") (pin "2") (pinfunction "2_2") (pintype "passive"))
      (node (ref "R9") (pin "2") (pinfunction "2_2") (pintype "passive"))
      (node (ref "TP5") (pin "1") (pinfunction "1_1") (pintype "passive"))
    )
    (net (code "20") (name "Net-(C8-Pad2)") (class "Default")
      (node (ref "C8") (pin "2") (pinfunction "2_2") (pintype "passive"))
      (node (ref "R15") (pin "2") (pinfunction "2_2") (pintype "passive"))
      (node (ref "R16") (pin "1") (pinfunction "1_1") (pintype "passive"))
      (node (ref "R18") (pin "2") (pinfunction "2_2") (pintype "passive"))
      (node (ref "TP6") (pin "1") (pinfunction "1_1") (pintype "passive"))
    )
    (net (code "21") (name "Net-(C11-Pad2)") (class "Default")
      (node (ref "C11") (pin "2") (pinfunction "2_2") (pintype "passive"))
      (node (ref "R21") (pin "2") (pinfunction "2_2") (pintype "passive"))
      (node (ref "R22") (pin "1") (pinfunction "1_1") (pintype "passive"))
      (node (ref "R23") (pin "2") (pinfunction "2_2") (pintype "passive"))
      (node (ref "TP10") (pin "1") (pinfunction "1_1") (pintype "passive"))
    )
    (net (code "22") (name "Net-(C14-Pad2)") (class "Default")
      (node (ref "C14") (pin "2") (pinfunction "2_2") (pintype "passive"))
      (node (ref "R27") (pin "2") (pinfunction "2_2") (pintype "passive"))
      (node (ref "R28") (pin "1") (pinfunction "1_1") (pintype "passive"))
      (node (ref "R30") (pin "2") (pinfunction "2_2") (pintype "passive"))
      (node (ref "TP11") (pin "1") (pinfunction "1_1") (pintype "passive"))
    )
    (net (code "23") (name "Net-(C17-Pad2)") (class "Default")
      (node (ref "C17") (pin "2") (pinfunction "2_2") (pintype "passive"))
      (node (ref "R33") (pin "2") (pinfunction "2_2") (pintype "passive"))
      (node (ref "R34") (pin "1") (pinfunction "1_1") (pintype "passive"))
      (node (ref "R35") (pin "2") (pinfunction "2_2") (pintype "passive"))
      (node (ref "TP15") (pin "1") (pinfunction "1_1") (pintype "passive"))
    )
    (net (code "24") (name "Net-(R1-Pad2)") (class "Default")
      (node (ref "R1") (pin "2") (pinfunction "2_2") (pintype "passive"))
      (node (ref "R2") (pin "1") (pinfunction "1_1") (pintype "passive"))
    )
    (net (code "25") (name "Net-(R2-Pad2)") (class "Default")
      (node (ref "R2") (pin "2") (pinfunction "2_2") (pintype "passive"))
      (node (ref "R3") (pin "1") (pinfunction "1_1") (pintype "passive"))
    )
    (net (code "26") (name "Net-(R7-Pad2)") (class "Default")
      (node (ref "R7") (pin "2") (pinfunction "2_2") (pintype "passive"))
      (node (ref "R8") (pin "1") (pinfunction "1_1") (pintype "passive"))
    )
    (net (code "27") (name "Net-(R8-Pad2)") (class "Default")
      (node (ref "R8") (pin "2") (pinfunction "2_2") (pintype "passive"))
      (node (ref "R9") (pin "1") (pinfunction "1_1") (pintype "passive"))
    )
    (net (code "28") (name "Net-(R13-Pad2)") (class "Default")
      (node (ref "R13") (pin "2") (pinfunction "2_2") (pintype "passive"))
      (node (ref "R14") (pin "1") (pinfunction "1_1") (pintype "passive"))
    )
    (net (code "29") (name "Net-(R14-Pad2)") (class "Default")
      (node (ref "R14") (pin "2") (pinfunction "2_2") (pintype "passive"))
      (node (ref "R15") (pin "1") (pinfunction "1_1") (pintype "passive"))
    )
    (net (code "30") (name "Net-(R19-Pad2)") (class "Default")
      (node (ref "R19") (pin "2") (pinfunction "2_2") (pintype "passive"))
      (node (ref "R20") (pin "1") (pinfunction "1_1") (pintype "passive"))
    )
    (net (code "31") (name "Net-(R20-Pad2)") (class "Default")
      (node (ref "R20") (pin "2") (pinfunction "2_2") (pintype "passive"))
      (node (ref "R21") (pin "1") (pinfunction "1_1") (pintype "passive"))
    )
    (net (code "32") (name "Net-(R25-Pad2)") (class "Default")
      (node (ref "R25") (pin "2") (pinfunction "2_2") (pintype "passive"))
      (node (ref "R26") (pin "1") (pinfunction "1_1") (pintype "passive"))
    )
    (net (code "33") (name "Net-(R26-Pad2)") (class "Default")
      (node (ref "R26") (pin "2") (pinfunction "2_2") (pintype "passive"))
      (node (ref "R27") (pin "1") (pinfunction "1_1") (pintype "passive"))
    )
    (net (code "34") (name "Net-(R31-Pad2)") (class "Default")
      (node (ref "R31") (pin "2") (pinfunction "2_2") (pintype "passive"))
      (node (ref "R32") (pin "1") (pinfunction "1_1") (pintype "passive"))
    )
    (net (code "35") (name "Net-(R32-Pad2)") (class "Default")
      (node (ref "R32") (pin "2") (pinfunction "2_2") (pintype "passive"))
      (node (ref "R33") (pin "1") (pinfunction "1_1") (pintype "passive"))
    )
    (net (code "36") (name "unconnected-(U1-NC-Pad5)") (class "Default")
      (node (ref "U1") (pin "5") (pinfunction "NC_5") (pintype "passive+no_connect"))
    )
    (net (code "37") (name "unconnected-(U1-Trim-Pad1)") (class "Default")
      (node (ref "U1") (pin "1") (pinfunction "Trim_1") (pintype "passive+no_connect"))
    )
    (net (code "38") (name "unconnected-(U1-Trim-Pad8)") (class "Default")
      (node (ref "U1") (pin "8") (pinfunction "Trim_8") (pintype "passive+no_connect"))
    )
    (net (code "39") (name "unconnected-(U2-NC-Pad5)") (class "Default")
      (node (ref "U2") (pin "5") (pinfunction "NC_5") (pintype "passive+no_connect"))
    )
    (net (code "40") (name "unconnected-(U2-Trim-Pad1)") (class "Default")
      (node (ref "U2") (pin "1") (pinfunction "Trim_1") (pintype "passive+no_connect"))
    )
    (net (code "41") (name "unconnected-(U2-Trim-Pad8)") (class "Default")
      (node (ref "U2") (pin "8") (pinfunction "Trim_8") (pintype "passive+no_connect"))
    )
    (net (code "42") (name "unconnected-(U3-NC-Pad5)") (class "Default")
      (node (ref "U3") (pin "5") (pinfunction "NC_5") (pintype "passive+no_connect"))
    )
    (net (code "43") (name "unconnected-(U3-Trim-Pad1)") (class "Default")
      (node (ref "U3") (pin "1") (pinfunction "Trim_1") (pintype "passive+no_connect"))
    )
    (net (code "44") (name "unconnected-(U3-Trim-Pad8)") (class "Default")
      (node (ref "U3") (pin "8") (pinfunction "Trim_8") (pintype "passive+no_connect"))
    )
  )
)
